# Copy_of_component_layout.net
KiCad netlist of a schematic drawn in Altium Designer
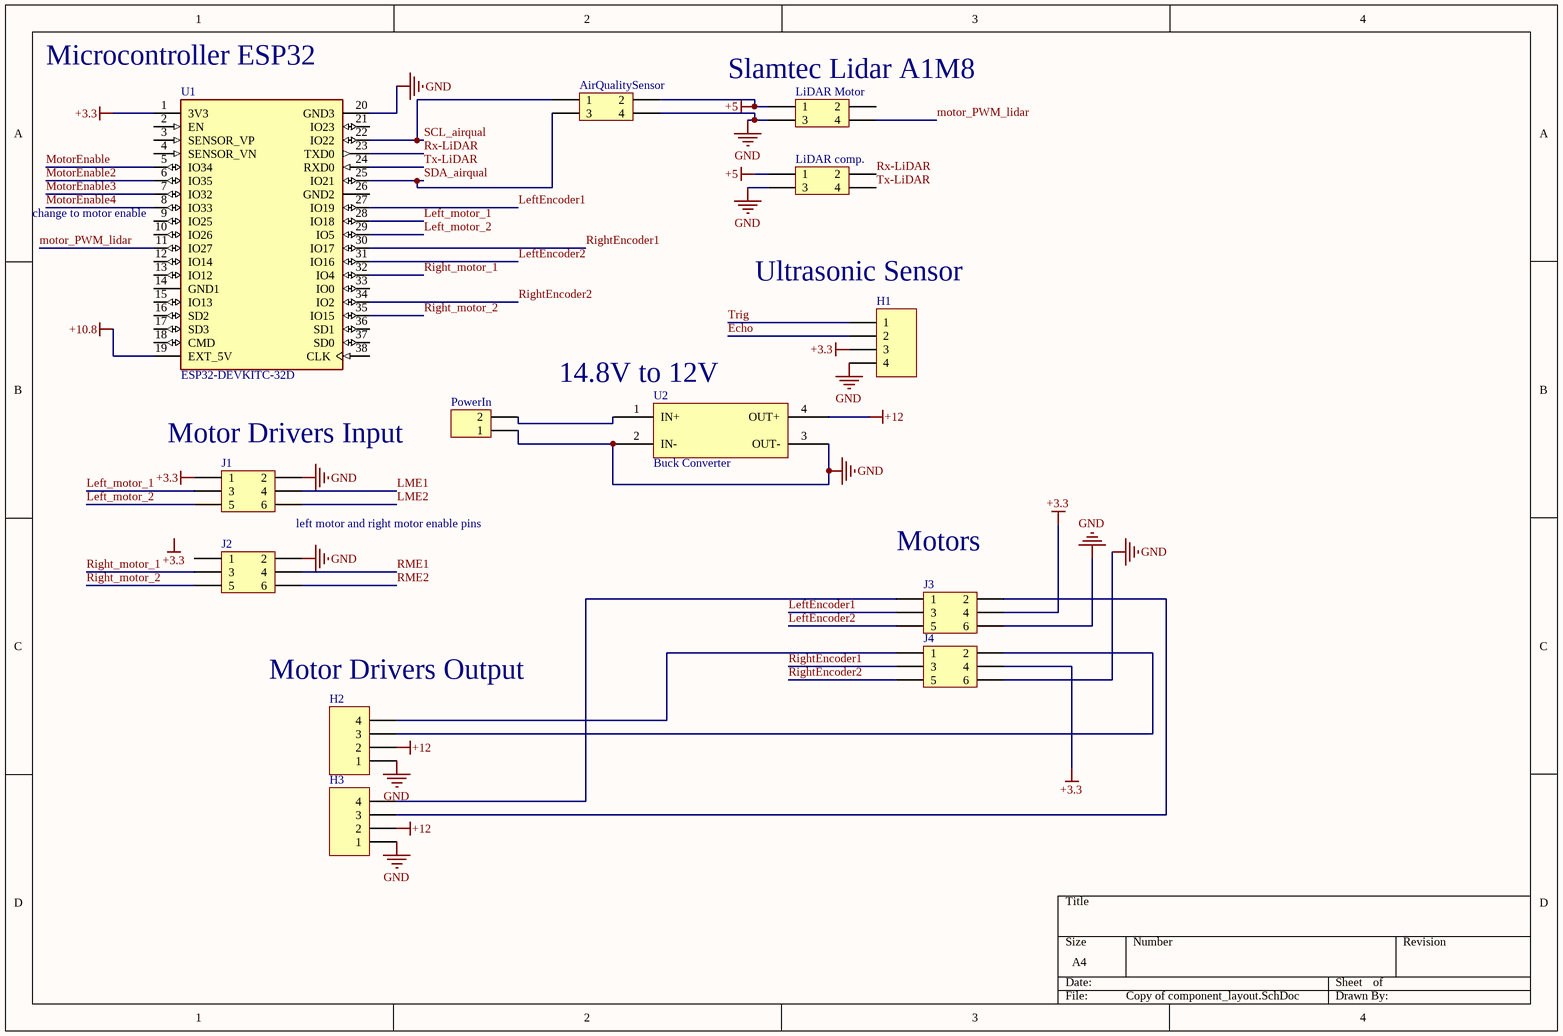
[diagram p0: Copy of component_layout.SchDoc]

(export (version "E")
  (design (tool "Eeschema 10.0.6"))
  (components
    (comp (ref "AirQualitySensor")
      (value "HEADER")
      (footprint "HDR2X2")
      (description "Header, 5-Pin, Dual row")
      (fields (field (name "PUBLISHER") "Altium Limited"))
      (libsource (lib "massey_libs") (part "Header 2x2"))
    )
    (comp (ref "H1")
      (value "Header 4")
      (footprint "HDR1X4")
      (description "Header, 4-Pin")
      (fields (field (name "MANUFACTURER") "Generic Components"))
      (libsource (lib "") (part "Header 4_1"))
    )
    (comp (ref "H2")
      (value "Header 4")
      (footprint "HDR1X4")
      (description "Header, 4-Pin")
      (fields (field (name "MANUFACTURER") "Generic Components"))
      (libsource (lib "massey_libs") (part "Header 4"))
    )
    (comp (ref "H3")
      (value "Header 4")
      (footprint "HDR1X4")
      (description "Header, 4-Pin")
      (fields (field (name "MANUFACTURER") "Generic Components"))
      (libsource (lib "massey_libs") (part "Header 4"))
    )
    (comp (ref "J1")
      (value "HEADER")
      (footprint "HDR2X3")
      (description "Header, 5-Pin, Dual row")
      (fields (field (name "PUBLISHER") "Altium Limited"))
      (libsource (lib "massey_libs") (part "Header 2x3"))
    )
    (comp (ref "J2")
      (value "HEADER")
      (footprint "HDR2X3")
      (description "Header, 5-Pin, Dual row")
      (fields (field (name "PUBLISHER") "Altium Limited"))
      (libsource (lib "massey_libs") (part "Header 2x3"))
    )
    (comp (ref "J3")
      (value "HEADER")
      (footprint "HDR2X3")
      (description "Header, 5-Pin, Dual row")
      (fields (field (name "PUBLISHER") "Altium Limited"))
      (libsource (lib "massey_libs") (part "Header 2x3"))
    )
    (comp (ref "J4")
      (value "HEADER")
      (footprint "HDR2X3")
      (description "Header, 5-Pin, Dual row")
      (fields (field (name "PUBLISHER") "Altium Limited"))
      (libsource (lib "massey_libs") (part "Header 2x3"))
    )
    (comp (ref "LiDAR comp.")
      (value "HEADER")
      (footprint "HDR2X2")
      (description "Header, 5-Pin, Dual row")
      (fields (field (name "PUBLISHER") "Altium Limited"))
      (libsource (lib "massey_libs") (part "Header 2x2"))
    )
    (comp (ref "LiDAR Motor")
      (value "HEADER")
      (footprint "HDR2X2")
      (description "Header, 5-Pin, Dual row")
      (fields (field (name "PUBLISHER") "Altium Limited"))
      (libsource (lib "massey_libs") (part "Header 2x2"))
    )
    (comp (ref "PowerIn")
      (value "Header 2")
      (footprint "HDR1X2")
      (description "Header, 2-Pin")
      (fields (field (name "MANUFACTURER") "Generic Components"))
      (libsource (lib "massey_libs") (part "Header 2"))
    )
    (comp (ref "U1")
      (value "ESP32-DEVKITC-32D")
      (footprint "MODULE_ESP32-DEVKITC-32D")
      (description "WiFi Development Tools (802.11) ESP32 General Development Kit, ESP32-WROOM-32D on the board")
      (fields (field (name "MF") "Espressif Systems"))
      (libsource (lib "ESP32-DEVKITC-32D") (part "ESP32-DEVKITC-32D"))
    )
    (comp (ref "U2")
      (value "Buck Converter")
      (footprint "Buck Converter")
      (description "Buck Convertor")
      (libsource (lib "massey_libs_extra") (part "Buck Converter"))
    )
  )
  (nets
    (net (code "1") (name "+3.3") (class "Default")
      (node (ref "H1") (pin "3") (pinfunction "3_3") (pintype "passive"))
      (node (ref "J1") (pin "1") (pinfunction "1_1") (pintype "passive"))
      (node (ref "J3") (pin "4") (pinfunction "4_4") (pintype "passive"))
      (node (ref "J4") (pin "4") (pinfunction "4_4") (pintype "passive"))
      (node (ref "U1") (pin "1") (pinfunction "3V3_1") (pintype "power_in"))
    )
    (net (code "2") (name "+5") (class "Default")
      (node (ref "AirQualitySensor") (pin "2") (pinfunction "2_2") (pintype "passive"))
      (node (ref "LiDAR Motor") (pin "1") (pinfunction "1_1") (pintype "passive"))
      (node (ref "LiDAR comp.") (pin "1") (pinfunction "1_1") (pintype "passive"))
    )
    (net (code "3") (name "+10.8") (class "Default")
      (node (ref "U1") (pin "19") (pinfunction "EXT_5V_19") (pintype "power_in"))
    )
    (net (code "4") (name "+12") (class "Default")
      (node (ref "H2") (pin "2") (pinfunction "2_2") (pintype "passive"))
      (node (ref "H3") (pin "2") (pinfunction "2_2") (pintype "passive"))
      (node (ref "U2") (pin "4") (pinfunction "OUT+_4") (pintype "power_in"))
    )
    (net (code "5") (name "/Echo") (class "Default")
      (node (ref "H1") (pin "2") (pinfunction "2_2") (pintype "passive"))
    )
    (net (code "6") (name "/LME1") (class "Default")
      (node (ref "J1") (pin "4") (pinfunction "4_4") (pintype "passive"))
    )
    (net (code "7") (name "/LME2") (class "Default")
      (node (ref "J1") (pin "6") (pinfunction "6_6") (pintype "passive"))
    )
    (net (code "8") (name "/LeftEncoder1") (class "Default")
      (node (ref "J3") (pin "3") (pinfunction "3_3") (pintype "passive"))
      (node (ref "U1") (pin "27") (pinfunction "IO19_27") (pintype "bidirectional"))
    )
    (net (code "9") (name "/LeftEncoder2") (class "Default")
      (node (ref "J3") (pin "5") (pinfunction "5_5") (pintype "passive"))
      (node (ref "U1") (pin "31") (pinfunction "IO16_31") (pintype "bidirectional"))
    )
    (net (code "10") (name "/Left_motor_1") (class "Default")
      (node (ref "J1") (pin "3") (pinfunction "3_3") (pintype "passive"))
      (node (ref "U1") (pin "28") (pinfunction "IO18_28") (pintype "bidirectional"))
    )
    (net (code "11") (name "/Left_motor_2") (class "Default")
      (node (ref "J1") (pin "5") (pinfunction "5_5") (pintype "passive"))
      (node (ref "U1") (pin "29") (pinfunction "IO5_29") (pintype "bidirectional"))
    )
    (net (code "12") (name "/MotorEnable") (class "Default")
      (node (ref "U1") (pin "5") (pinfunction "IO34_5") (pintype "bidirectional"))
    )
    (net (code "13") (name "/MotorEnable2") (class "Default")
      (node (ref "U1") (pin "6") (pinfunction "IO35_6") (pintype "bidirectional"))
    )
    (net (code "14") (name "/MotorEnable3") (class "Default")
      (node (ref "U1") (pin "7") (pinfunction "IO32_7") (pintype "bidirectional"))
    )
    (net (code "15") (name "/MotorEnable4") (class "Default")
      (node (ref "U1") (pin "8") (pinfunction "IO33_8") (pintype "bidirectional"))
    )
    (net (code "16") (name "/RME1") (class "Default")
      (node (ref "J2") (pin "4") (pinfunction "4_4") (pintype "passive"))
    )
    (net (code "17") (name "/RME2") (class "Default")
      (node (ref "J2") (pin "6") (pinfunction "6_6") (pintype "passive"))
    )
    (net (code "18") (name "/RightEncoder1") (class "Default")
      (node (ref "J4") (pin "3") (pinfunction "3_3") (pintype "passive"))
      (node (ref "U1") (pin "30") (pinfunction "IO17_30") (pintype "bidirectional"))
    )
    (net (code "19") (name "/RightEncoder2") (class "Default")
      (node (ref "J4") (pin "5") (pinfunction "5_5") (pintype "passive"))
      (node (ref "U1") (pin "34") (pinfunction "IO2_34") (pintype "bidirectional"))
    )
    (net (code "20") (name "/Right_motor_1") (class "Default")
      (node (ref "J2") (pin "3") (pinfunction "3_3") (pintype "passive"))
      (node (ref "U1") (pin "32") (pinfunction "IO4_32") (pintype "bidirectional"))
    )
    (net (code "21") (name "/Right_motor_2") (class "Default")
      (node (ref "J2") (pin "5") (pinfunction "5_5") (pintype "passive"))
      (node (ref "U1") (pin "35") (pinfunction "IO15_35") (pintype "bidirectional"))
    )
    (net (code "22") (name "/Rx-LiDAR") (class "Default")
      (node (ref "LiDAR comp.") (pin "2") (pinfunction "2_2") (pintype "passive"))
      (node (ref "U1") (pin "23") (pinfunction "TXD0_23") (pintype "output"))
    )
    (net (code "23") (name "/SCL_airqual") (class "Default")
      (node (ref "AirQualitySensor") (pin "1") (pinfunction "1_1") (pintype "passive"))
      (node (ref "U1") (pin "22") (pinfunction "IO22_22") (pintype "bidirectional"))
    )
    (net (code "24") (name "/SDA_airqual") (class "Default")
      (node (ref "AirQualitySensor") (pin "3") (pinfunction "3_3") (pintype "passive"))
      (node (ref "U1") (pin "25") (pinfunction "IO21_25") (pintype "bidirectional"))
    )
    (net (code "25") (name "/Trig") (class "Default")
      (node (ref "H1") (pin "1") (pinfunction "1_1") (pintype "passive"))
    )
    (net (code "26") (name "/Tx-LiDAR") (class "Default")
      (node (ref "LiDAR comp.") (pin "4") (pinfunction "4_4") (pintype "passive"))
      (node (ref "U1") (pin "24") (pinfunction "RXD0_24") (pintype "input"))
    )
    (net (code "27") (name "/motor_PWM_lidar") (class "Default")
      (node (ref "LiDAR Motor") (pin "4") (pinfunction "4_4") (pintype "passive"))
      (node (ref "U1") (pin "11") (pinfunction "IO27_11") (pintype "bidirectional"))
    )
    (net (code "28") (name "GND") (class "Default")
      (node (ref "AirQualitySensor") (pin "4") (pinfunction "4_4") (pintype "passive"))
      (node (ref "H1") (pin "4") (pinfunction "4_4") (pintype "passive"))
      (node (ref "H2") (pin "1") (pinfunction "1_1") (pintype "passive"))
      (node (ref "H3") (pin "1") (pinfunction "1_1") (pintype "passive"))
      (node (ref "J1") (pin "2") (pinfunction "2_2") (pintype "passive"))
      (node (ref "J2") (pin "2") (pinfunction "2_2") (pintype "passive"))
      (node (ref "J3") (pin "6") (pinfunction "6_6") (pintype "passive"))
      (node (ref "J4") (pin "6") (pinfunction "6_6") (pintype "passive"))
      (node (ref "LiDAR Motor") (pin "3") (pinfunction "3_3") (pintype "passive"))
      (node (ref "LiDAR comp.") (pin "3") (pinfunction "3_3") (pintype "passive"))
      (node (ref "PowerIn") (pin "1") (pinfunction "1_1") (pintype "passive"))
      (node (ref "U1") (pin "20") (pinfunction "GND3_20") (pintype "power_in"))
      (node (ref "U2") (pin "2") (pinfunction "IN-_2") (pintype "power_in"))
      (node (ref "U2") (pin "3") (pinfunction "OUT-_3") (pintype "power_in"))
    )
    (net (code "29") (name "Net-(H2-Pad3)") (class "Default")
      (node (ref "H2") (pin "3") (pinfunction "3_3") (pintype "passive"))
      (node (ref "J4") (pin "2") (pinfunction "2_2") (pintype "passive"))
    )
    (net (code "30") (name "Net-(H2-Pad4)") (class "Default")
      (node (ref "H2") (pin "4") (pinfunction "4_4") (pintype "passive"))
      (node (ref "J4") (pin "1") (pinfunction "1_1") (pintype "passive"))
    )
    (net (code "31") (name "Net-(H3-Pad3)") (class "Default")
      (node (ref "H3") (pin "3") (pinfunction "3_3") (pintype "passive"))
      (node (ref "J3") (pin "2") (pinfunction "2_2") (pintype "passive"))
    )
    (net (code "32") (name "Net-(H3-Pad4)") (class "Default")
      (node (ref "H3") (pin "4") (pinfunction "4_4") (pintype "passive"))
      (node (ref "J3") (pin "1") (pinfunction "1_1") (pintype "passive"))
    )
    (net (code "33") (name "Net-(U2-IN+)") (class "Default")
      (node (ref "PowerIn") (pin "2") (pinfunction "2_2") (pintype "passive"))
      (node (ref "U2") (pin "1") (pinfunction "IN+_1") (pintype "power_in"))
    )
    (net (code "34") (name "unconnected-(J2-Pad1)") (class "Default")
      (node (ref "J2") (pin "1") (pinfunction "1_1") (pintype "passive"))
    )
    (net (code "35") (name "unconnected-(LiDAR Motor-Pad2)") (class "Default")
      (node (ref "LiDAR Motor") (pin "2") (pinfunction "2_2") (pintype "passive"))
    )
    (net (code "36") (name "unconnected-(U1-CLK-Pad38)") (class "Default")
      (node (ref "U1") (pin "38") (pinfunction "CLK_38") (pintype "input"))
    )
    (net (code "37") (name "unconnected-(U1-CMD-Pad18)") (class "Default")
      (node (ref "U1") (pin "18") (pinfunction "CMD_18") (pintype "bidirectional"))
    )
    (net (code "38") (name "unconnected-(U1-EN-Pad2)") (class "Default")
      (node (ref "U1") (pin "2") (pinfunction "EN_2") (pintype "input"))
    )
    (net (code "39") (name "unconnected-(U1-GND1-Pad14)") (class "Default")
      (node (ref "U1") (pin "14") (pinfunction "GND1_14") (pintype "power_in"))
    )
    (net (code "40") (name "unconnected-(U1-GND2-Pad26)") (class "Default")
      (node (ref "U1") (pin "26") (pinfunction "GND2_26") (pintype "power_in"))
    )
    (net (code "41") (name "unconnected-(U1-IO0-Pad33)") (class "Default")
      (node (ref "U1") (pin "33") (pinfunction "IO0_33") (pintype "bidirectional"))
    )
    (net (code "42") (name "unconnected-(U1-IO12-Pad13)") (class "Default")
      (node (ref "U1") (pin "13") (pinfunction "IO12_13") (pintype "bidirectional"))
    )
    (net (code "43") (name "unconnected-(U1-IO13-Pad15)") (class "Default")
      (node (ref "U1") (pin "15") (pinfunction "IO13_15") (pintype "bidirectional"))
    )
    (net (code "44") (name "unconnected-(U1-IO14-Pad12)") (class "Default")
      (node (ref "U1") (pin "12") (pinfunction "IO14_12") (pintype "bidirectional"))
    )
    (net (code "45") (name "unconnected-(U1-IO23-Pad21)") (class "Default")
      (node (ref "U1") (pin "21") (pinfunction "IO23_21") (pintype "bidirectional"))
    )
    (net (code "46") (name "unconnected-(U1-IO25-Pad9)") (class "Default")
      (node (ref "U1") (pin "9") (pinfunction "IO25_9") (pintype "bidirectional"))
    )
    (net (code "47") (name "unconnected-(U1-IO26-Pad10)") (class "Default")
      (node (ref "U1") (pin "10") (pinfunction "IO26_10") (pintype "bidirectional"))
    )
    (net (code "48") (name "unconnected-(U1-SD0-Pad37)") (class "Default")
      (node (ref "U1") (pin "37") (pinfunction "SD0_37") (pintype "bidirectional"))
    )
    (net (code "49") (name "unconnected-(U1-SD1-Pad36)") (class "Default")
      (node (ref "U1") (pin "36") (pinfunction "SD1_36") (pintype "bidirectional"))
    )
    (net (code "50") (name "unconnected-(U1-SD2-Pad16)") (class "Default")
      (node (ref "U1") (pin "16") (pinfunction "SD2_16") (pintype "bidirectional"))
    )
    (net (code "51") (name "unconnected-(U1-SD3-Pad17)") (class "Default")
      (node (ref "U1") (pin "17") (pinfunction "SD3_17") (pintype "bidirectional"))
    )
    (net (code "52") (name "unconnected-(U1-SENSOR_VN-Pad4)") (class "Default")
      (node (ref "U1") (pin "4") (pinfunction "SENSOR_VN_4") (pintype "input"))
    )
    (net (code "53") (name "unconnected-(U1-SENSOR_VP-Pad3)") (class "Default")
      (node (ref "U1") (pin "3") (pinfunction "SENSOR_VP_3") (pintype "input"))
    )
  )
)
